# SHDN-BSPD-S05-V00-Microcontroller.net
KiCad netlist of a schematic drawn in Altium Designer
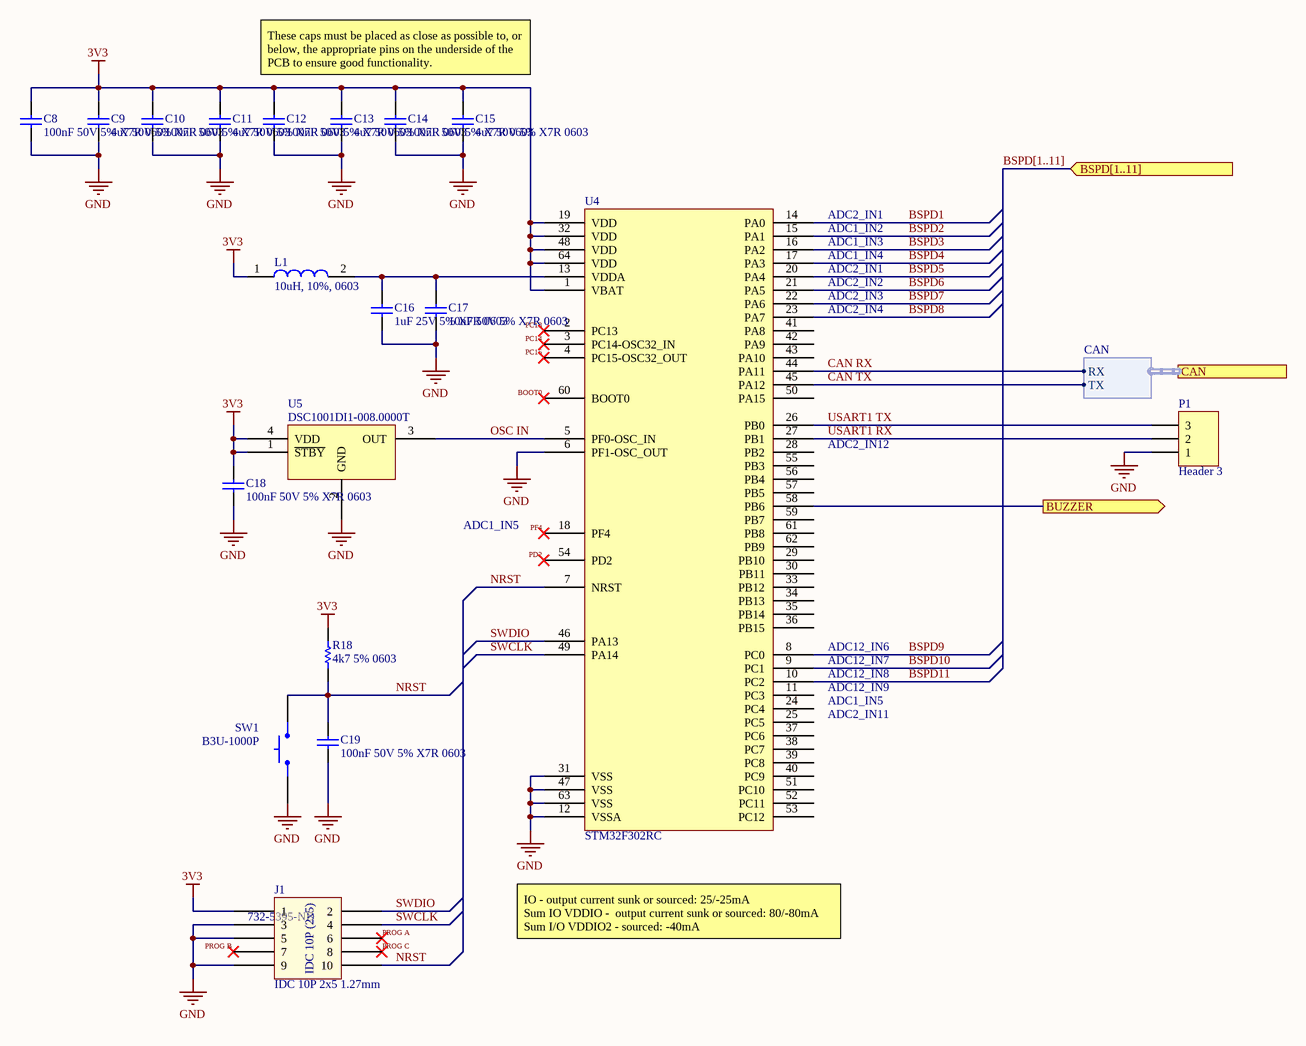
[diagram p0: SHDN-BSPD-S05-V00-Microcontroller.SchDoc]

(export (version "E")
  (design (tool "Eeschema 10.0.6"))
  (components
    (comp (ref "C8")
      (value "100nF 50V 5% X7R 0603")
      (footprint "Cap_Ceramic_0603")
      (description "Capacitor, Ceramic, SMD, 100nF, 50V, 5%, X7R, 0603")
      (libsource (lib "StandardCapacitors") (part "100nF 50V 5% X7R 0603"))
    )
    (comp (ref "C9")
      (value "4u7 50V 5% X7R 0603")
      (footprint "Cap_Ceramic_0603")
      (description "Capacitor, Ceramic, SMD, 4u7, 50V, 5%, X7R, 0603")
      (libsource (lib "StandardCapacitors") (part "4u7 50V 5% X7R 0603"))
    )
    (comp (ref "C10")
      (value "100nF 50V 5% X7R 0603")
      (footprint "Cap_Ceramic_0603")
      (description "Capacitor, Ceramic, SMD, 100nF, 50V, 5%, X7R, 0603")
      (libsource (lib "StandardCapacitors") (part "100nF 50V 5% X7R 0603"))
    )
    (comp (ref "C11")
      (value "4u7 50V 5% X7R 0603")
      (footprint "Cap_Ceramic_0603")
      (description "Capacitor, Ceramic, SMD, 4u7, 50V, 5%, X7R, 0603")
      (libsource (lib "StandardCapacitors") (part "4u7 50V 5% X7R 0603"))
    )
    (comp (ref "C12")
      (value "100nF 50V 5% X7R 0603")
      (footprint "Cap_Ceramic_0603")
      (description "Capacitor, Ceramic, SMD, 100nF, 50V, 5%, X7R, 0603")
      (libsource (lib "StandardCapacitors") (part "100nF 50V 5% X7R 0603"))
    )
    (comp (ref "C13")
      (value "4u7 50V 5% X7R 0603")
      (footprint "Cap_Ceramic_0603")
      (description "Capacitor, Ceramic, SMD, 4u7, 50V, 5%, X7R, 0603")
      (libsource (lib "StandardCapacitors") (part "4u7 50V 5% X7R 0603"))
    )
    (comp (ref "C14")
      (value "100nF 50V 5% X7R 0603")
      (footprint "Cap_Ceramic_0603")
      (description "Capacitor, Ceramic, SMD, 100nF, 50V, 5%, X7R, 0603")
      (libsource (lib "StandardCapacitors") (part "100nF 50V 5% X7R 0603"))
    )
    (comp (ref "C15")
      (value "4u7 50V 5% X7R 0603")
      (footprint "Cap_Ceramic_0603")
      (description "Capacitor, Ceramic, SMD, 4u7, 50V, 5%, X7R, 0603")
      (libsource (lib "StandardCapacitors") (part "4u7 50V 5% X7R 0603"))
    )
    (comp (ref "C16")
      (value "1uF 25V 5% X7R 0603")
      (footprint "Cap_Ceramic_0603")
      (description "Capacitor, Ceramic, SMD, 1uF, 25V, 5%, X7R, 0603")
      (libsource (lib "StandardCapacitors") (part "1uF 25V 5% X7R 0603"))
    )
    (comp (ref "C17")
      (value "10nF 50V 5% X7R 0603")
      (footprint "Cap_Ceramic_0603")
      (description "Capacitor, Ceramic, SMD, 10nF, 50V, 5%, X7R, 0603")
      (libsource (lib "StandardCapacitors") (part "10nF 50V 5% X7R 0603"))
    )
    (comp (ref "C18")
      (value "100nF 50V 5% X7R 0603")
      (footprint "Cap_Ceramic_0603")
      (description "Capacitor, Ceramic, SMD, 100nF, 50V, 5%, X7R, 0603")
      (libsource (lib "StandardCapacitors") (part "100nF 50V 5% X7R 0603"))
    )
    (comp (ref "C19")
      (value "100nF 50V 5% X7R 0603")
      (footprint "Cap_Ceramic_0603")
      (description "Capacitor, Ceramic, SMD, 100nF, 50V, 5%, X7R, 0603")
      (libsource (lib "StandardCapacitors") (part "100nF 50V 5% X7R 0603"))
    )
    (comp (ref "J1")
      (value "IDC 10P 2x5 1.27mm")
      (footprint "IDC 1.27MM 10P")
      (libsource (lib "IDCConnectors") (part "IDC 10P 2x5 1.27mm"))
    )
    (comp (ref "L1")
      (value "10uH, 10%, 0603")
      (footprint "Inductor_0603")
      (libsource (lib "QUTMS_InductorLibrary") (part "10uH, 10%, 0603"))
    )
    (comp (ref "P1")
      (value "Header 3")
      (footprint "HDR1X3")
      (description "Header, 3-Pin")
      (fields (field (name "PUBLISHER") "Altium Limited"))
      (libsource (lib "Miscellaneous Connectors") (part "Header 3"))
    )
    (comp (ref "R18")
      (value "4k7 5% 0603")
      (footprint "Res_ThinFilm_0603")
      (description "Resistor, SMD, 4k7, 0.1W, 5%, 0603")
      (libsource (lib "StandardResistors") (part "4k7 5% 0603"))
    )
    (comp (ref "SW1")
      (value "B3U-1000P")
      (footprint "BTN B3U-1000P")
      (description "Omron B3U-1000P Ultra Miniture Switch")
      (libsource (lib "QUTMS_SwitchLibrary") (part "BTN B3U-1000P"))
    )
    (comp (ref "U4")
      (value "STM32F302RC")
      (footprint "STM32F302RC")
      (description "ARM® Cortex®-M4 STM32F3 Microcontroller IC 32-Bit 72MHz 256KB (256K x 8) FLASH 64-LQFP (10x10)")
      (libsource (lib "QUTMS_STM32Library") (part "STM32F302RC"))
    )
    (comp (ref "U5")
      (value "DSC1001DI1-008.0000T")
      (footprint "DSC1001DI1-008.0000TCT-ND")
      (description "8MHz XO (Standard) CMOS Oscillator 1.8 ~ 3.3V Standby (Power Down) 4-SMD, No Lead")
      (libsource (lib "QUTMS_CrystalLibrary") (part "DSC1001DI1-008.0000T"))
    )
  )
  (nets
    (net (code "2") (name "/BOOT0") (class "Default")
      (node (ref "U4") (pin "60") (pinfunction "BOOT0_60") (pintype "passive+no_connect"))
    )
    (net (code "3") (name "/BSPD1") (class "Default")
      (node (ref "U4") (pin "14") (pinfunction "PA0_14") (pintype "passive"))
    )
    (net (code "4") (name "/BSPD2") (class "Default")
      (node (ref "U4") (pin "15") (pinfunction "PA1_15") (pintype "passive"))
    )
    (net (code "5") (name "/BSPD3") (class "Default")
      (node (ref "U4") (pin "16") (pinfunction "PA2_16") (pintype "passive"))
    )
    (net (code "6") (name "/BSPD4") (class "Default")
      (node (ref "U4") (pin "17") (pinfunction "PA3_17") (pintype "passive"))
    )
    (net (code "7") (name "/BSPD5") (class "Default")
      (node (ref "U4") (pin "20") (pinfunction "PA4_20") (pintype "passive"))
    )
    (net (code "8") (name "/BSPD6") (class "Default")
      (node (ref "U4") (pin "21") (pinfunction "PA5_21") (pintype "passive"))
    )
    (net (code "9") (name "/BSPD7") (class "Default")
      (node (ref "U4") (pin "22") (pinfunction "PA6_22") (pintype "passive"))
    )
    (net (code "10") (name "/BSPD8") (class "Default")
      (node (ref "U4") (pin "23") (pinfunction "PA7_23") (pintype "passive"))
    )
    (net (code "11") (name "/BSPD9") (class "Default")
      (node (ref "U4") (pin "8") (pinfunction "PC0_8") (pintype "passive"))
    )
    (net (code "12") (name "/BSPD10") (class "Default")
      (node (ref "U4") (pin "9") (pinfunction "PC1_9") (pintype "passive"))
    )
    (net (code "13") (name "/BSPD11") (class "Default")
      (node (ref "U4") (pin "10") (pinfunction "PC2_10") (pintype "passive"))
    )
    (net (code "15") (name "/BUZZER") (class "Default")
      (node (ref "U4") (pin "58") (pinfunction "PB6_58") (pintype "passive"))
    )
    (net (code "16") (name "/CAN RX") (class "Default")
      (node (ref "U4") (pin "44") (pinfunction "PA11_44") (pintype "passive"))
    )
    (net (code "17") (name "/CAN TX") (class "Default")
      (node (ref "U4") (pin "45") (pinfunction "PA12_45") (pintype "passive"))
    )
    (net (code "18") (name "/NRST") (class "Default")
      (node (ref "C19") (pin "2") (pinfunction "2_2") (pintype "passive"))
      (node (ref "J1") (pin "10") (pinfunction "10_10") (pintype "passive"))
      (node (ref "R18") (pin "1") (pinfunction "1_1") (pintype "passive"))
      (node (ref "SW1") (pin "2") (pinfunction "2_2") (pintype "passive"))
      (node (ref "U4") (pin "7") (pinfunction "NRST_7") (pintype "passive"))
    )
    (net (code "19") (name "/OSC IN") (class "Default")
      (node (ref "U4") (pin "5") (pinfunction "PF0-OSC_IN_5") (pintype "passive"))
      (node (ref "U5") (pin "3") (pinfunction "OUT_3") (pintype "passive"))
    )
    (net (code "20") (name "/PC13") (class "Default")
      (node (ref "U4") (pin "2") (pinfunction "PC13_2") (pintype "passive+no_connect"))
    )
    (net (code "21") (name "/PC14") (class "Default")
      (node (ref "U4") (pin "3") (pinfunction "PC14-OSC32_IN_3") (pintype "passive+no_connect"))
    )
    (net (code "22") (name "/PC15") (class "Default")
      (node (ref "U4") (pin "4") (pinfunction "PC15-OSC32_OUT_4") (pintype "passive+no_connect"))
    )
    (net (code "23") (name "/PD2") (class "Default")
      (node (ref "U4") (pin "54") (pinfunction "PD2_54") (pintype "passive+no_connect"))
    )
    (net (code "24") (name "/PF4") (class "Default")
      (node (ref "U4") (pin "18") (pinfunction "PF4_18") (pintype "passive+no_connect"))
    )
    (net (code "25") (name "/PROG A") (class "Default")
      (node (ref "J1") (pin "6") (pinfunction "6_6") (pintype "passive+no_connect"))
    )
    (net (code "26") (name "/PROG B") (class "Default")
      (node (ref "J1") (pin "7") (pinfunction "7_7") (pintype "passive+no_connect"))
    )
    (net (code "27") (name "/PROG C") (class "Default")
      (node (ref "J1") (pin "8") (pinfunction "8_8") (pintype "passive+no_connect"))
    )
    (net (code "28") (name "/SWCLK") (class "Default")
      (node (ref "J1") (pin "4") (pinfunction "4_4") (pintype "passive"))
      (node (ref "U4") (pin "49") (pinfunction "PA14_49") (pintype "passive"))
    )
    (net (code "29") (name "/SWDIO") (class "Default")
      (node (ref "J1") (pin "2") (pinfunction "2_2") (pintype "passive"))
      (node (ref "U4") (pin "46") (pinfunction "PA13_46") (pintype "passive"))
    )
    (net (code "30") (name "/USART1 RX") (class "Default")
      (node (ref "P1") (pin "2") (pinfunction "2_2") (pintype "passive"))
      (node (ref "U4") (pin "27") (pinfunction "PB1_27") (pintype "passive"))
    )
    (net (code "31") (name "/USART1 TX") (class "Default")
      (node (ref "P1") (pin "3") (pinfunction "3_3") (pintype "passive"))
      (node (ref "U4") (pin "26") (pinfunction "PB0_26") (pintype "passive"))
    )
    (net (code "33") (name "3V3") (class "Default")
      (node (ref "C10") (pin "2") (pinfunction "2_2") (pintype "passive"))
      (node (ref "C11") (pin "2") (pinfunction "2_2") (pintype "passive"))
      (node (ref "C12") (pin "2") (pinfunction "2_2") (pintype "passive"))
      (node (ref "C13") (pin "2") (pinfunction "2_2") (pintype "passive"))
      (node (ref "C14") (pin "2") (pinfunction "2_2") (pintype "passive"))
      (node (ref "C15") (pin "2") (pinfunction "2_2") (pintype "passive"))
      (node (ref "C18") (pin "2") (pinfunction "2_2") (pintype "passive"))
      (node (ref "C8") (pin "2") (pinfunction "2_2") (pintype "passive"))
      (node (ref "C9") (pin "2") (pinfunction "2_2") (pintype "passive"))
      (node (ref "J1") (pin "1") (pinfunction "1_1") (pintype "passive"))
      (node (ref "L1") (pin "1") (pinfunction "1_1") (pintype "passive"))
      (node (ref "R18") (pin "2") (pinfunction "2_2") (pintype "passive"))
      (node (ref "U4") (pin "1") (pinfunction "VBAT_1") (pintype "passive"))
      (node (ref "U4") (pin "19") (pinfunction "VDD_19") (pintype "passive"))
      (node (ref "U4") (pin "32") (pinfunction "VDD_32") (pintype "passive"))
      (node (ref "U4") (pin "48") (pinfunction "VDD_48") (pintype "passive"))
      (node (ref "U4") (pin "64") (pinfunction "VDD_64") (pintype "passive"))
      (node (ref "U5") (pin "1") (pinfunction "~{STBY}_1") (pintype "passive"))
      (node (ref "U5") (pin "4") (pinfunction "VDD_4") (pintype "passive"))
    )
    (net (code "34") (name "GND") (class "Default")
      (node (ref "C10") (pin "1") (pinfunction "1_1") (pintype "passive"))
      (node (ref "C11") (pin "1") (pinfunction "1_1") (pintype "passive"))
      (node (ref "C12") (pin "1") (pinfunction "1_1") (pintype "passive"))
      (node (ref "C13") (pin "1") (pinfunction "1_1") (pintype "passive"))
      (node (ref "C14") (pin "1") (pinfunction "1_1") (pintype "passive"))
      (node (ref "C15") (pin "1") (pinfunction "1_1") (pintype "passive"))
      (node (ref "C16") (pin "1") (pinfunction "1_1") (pintype "passive"))
      (node (ref "C17") (pin "1") (pinfunction "1_1") (pintype "passive"))
      (node (ref "C18") (pin "1") (pinfunction "1_1") (pintype "passive"))
      (node (ref "C19") (pin "1") (pinfunction "1_1") (pintype "passive"))
      (node (ref "C8") (pin "1") (pinfunction "1_1") (pintype "passive"))
      (node (ref "C9") (pin "1") (pinfunction "1_1") (pintype "passive"))
      (node (ref "J1") (pin "3") (pinfunction "3_3") (pintype "passive"))
      (node (ref "J1") (pin "5") (pinfunction "5_5") (pintype "passive"))
      (node (ref "J1") (pin "9") (pinfunction "9_9") (pintype "passive"))
      (node (ref "P1") (pin "1") (pinfunction "1_1") (pintype "passive"))
      (node (ref "SW1") (pin "1") (pinfunction "1_1") (pintype "passive"))
      (node (ref "U4") (pin "12") (pinfunction "VSSA_12") (pintype "passive"))
      (node (ref "U4") (pin "31") (pinfunction "VSS_31") (pintype "passive"))
      (node (ref "U4") (pin "47") (pinfunction "VSS_47") (pintype "passive"))
      (node (ref "U4") (pin "6") (pinfunction "PF1-OSC_OUT_6") (pintype "passive"))
      (node (ref "U4") (pin "63") (pinfunction "VSS_63") (pintype "passive"))
      (node (ref "U5") (pin "2") (pinfunction "GND_2") (pintype "passive"))
    )
    (net (code "35") (name "Net-(U4-VDDA)") (class "Default")
      (node (ref "C16") (pin "2") (pinfunction "2_2") (pintype "passive"))
      (node (ref "C17") (pin "2") (pinfunction "2_2") (pintype "passive"))
      (node (ref "L1") (pin "2") (pinfunction "2_2") (pintype "passive"))
      (node (ref "U4") (pin "13") (pinfunction "VDDA_13") (pintype "passive"))
    )
    (net (code "36") (name "unconnected-(U4-PA8-Pad41)") (class "Default")
      (node (ref "U4") (pin "41") (pinfunction "PA8_41") (pintype "passive"))
    )
    (net (code "37") (name "unconnected-(U4-PA9-Pad42)") (class "Default")
      (node (ref "U4") (pin "42") (pinfunction "PA9_42") (pintype "passive"))
    )
    (net (code "38") (name "unconnected-(U4-PA10-Pad43)") (class "Default")
      (node (ref "U4") (pin "43") (pinfunction "PA10_43") (pintype "passive"))
    )
    (net (code "39") (name "unconnected-(U4-PA15-Pad50)") (class "Default")
      (node (ref "U4") (pin "50") (pinfunction "PA15_50") (pintype "passive"))
    )
    (net (code "40") (name "unconnected-(U4-PB2-Pad28)") (class "Default")
      (node (ref "U4") (pin "28") (pinfunction "PB2_28") (pintype "passive"))
    )
    (net (code "41") (name "unconnected-(U4-PB3-Pad55)") (class "Default")
      (node (ref "U4") (pin "55") (pinfunction "PB3_55") (pintype "passive"))
    )
    (net (code "42") (name "unconnected-(U4-PB4-Pad56)") (class "Default")
      (node (ref "U4") (pin "56") (pinfunction "PB4_56") (pintype "passive"))
    )
    (net (code "43") (name "unconnected-(U4-PB5-Pad57)") (class "Default")
      (node (ref "U4") (pin "57") (pinfunction "PB5_57") (pintype "passive"))
    )
    (net (code "44") (name "unconnected-(U4-PB7-Pad59)") (class "Default")
      (node (ref "U4") (pin "59") (pinfunction "PB7_59") (pintype "passive"))
    )
    (net (code "45") (name "unconnected-(U4-PB8-Pad61)") (class "Default")
      (node (ref "U4") (pin "61") (pinfunction "PB8_61") (pintype "passive"))
    )
    (net (code "46") (name "unconnected-(U4-PB9-Pad62)") (class "Default")
      (node (ref "U4") (pin "62") (pinfunction "PB9_62") (pintype "passive"))
    )
    (net (code "47") (name "unconnected-(U4-PB10-Pad29)") (class "Default")
      (node (ref "U4") (pin "29") (pinfunction "PB10_29") (pintype "passive"))
    )
    (net (code "48") (name "unconnected-(U4-PB11-Pad30)") (class "Default")
      (node (ref "U4") (pin "30") (pinfunction "PB11_30") (pintype "passive"))
    )
    (net (code "49") (name "unconnected-(U4-PB12-Pad33)") (class "Default")
      (node (ref "U4") (pin "33") (pinfunction "PB12_33") (pintype "passive"))
    )
    (net (code "50") (name "unconnected-(U4-PB13-Pad34)") (class "Default")
      (node (ref "U4") (pin "34") (pinfunction "PB13_34") (pintype "passive"))
    )
    (net (code "51") (name "unconnected-(U4-PB14-Pad35)") (class "Default")
      (node (ref "U4") (pin "35") (pinfunction "PB14_35") (pintype "passive"))
    )
    (net (code "52") (name "unconnected-(U4-PB15-Pad36)") (class "Default")
      (node (ref "U4") (pin "36") (pinfunction "PB15_36") (pintype "passive"))
    )
    (net (code "53") (name "unconnected-(U4-PC3-Pad11)") (class "Default")
      (node (ref "U4") (pin "11") (pinfunction "PC3_11") (pintype "passive"))
    )
    (net (code "54") (name "unconnected-(U4-PC4-Pad24)") (class "Default")
      (node (ref "U4") (pin "24") (pinfunction "PC4_24") (pintype "passive"))
    )
    (net (code "55") (name "unconnected-(U4-PC5-Pad25)") (class "Default")
      (node (ref "U4") (pin "25") (pinfunction "PC5_25") (pintype "passive"))
    )
    (net (code "56") (name "unconnected-(U4-PC6-Pad37)") (class "Default")
      (node (ref "U4") (pin "37") (pinfunction "PC6_37") (pintype "passive"))
    )
    (net (code "57") (name "unconnected-(U4-PC7-Pad38)") (class "Default")
      (node (ref "U4") (pin "38") (pinfunction "PC7_38") (pintype "passive"))
    )
    (net (code "58") (name "unconnected-(U4-PC8-Pad39)") (class "Default")
      (node (ref "U4") (pin "39") (pinfunction "PC8_39") (pintype "passive"))
    )
    (net (code "59") (name "unconnected-(U4-PC9-Pad40)") (class "Default")
      (node (ref "U4") (pin "40") (pinfunction "PC9_40") (pintype "passive"))
    )
    (net (code "60") (name "unconnected-(U4-PC10-Pad51)") (class "Default")
      (node (ref "U4") (pin "51") (pinfunction "PC10_51") (pintype "passive"))
    )
    (net (code "61") (name "unconnected-(U4-PC11-Pad52)") (class "Default")
      (node (ref "U4") (pin "52") (pinfunction "PC11_52") (pintype "passive"))
    )
    (net (code "62") (name "unconnected-(U4-PC12-Pad53)") (class "Default")
      (node (ref "U4") (pin "53") (pinfunction "PC12_53") (pintype "passive"))
    )
  )
)
